# Glue.net
KiCad netlist of a schematic drawn in Altium Designer
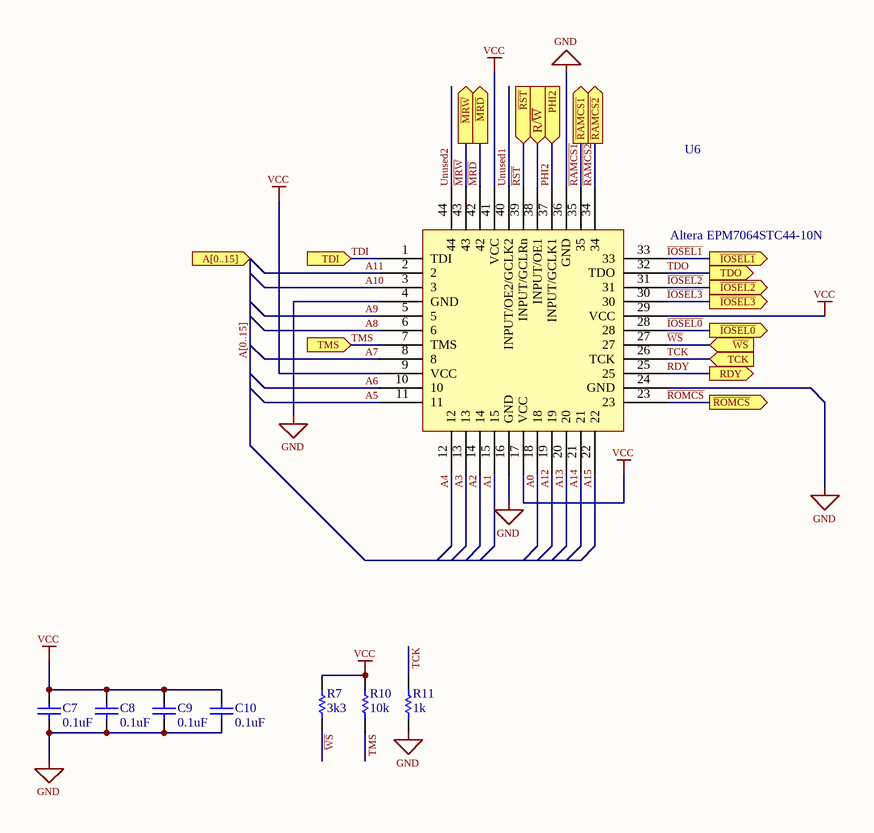
[diagram p0: Glue.SchDoc]

(export (version "E")
  (design (tool "Eeschema 10.0.6"))
  (components
    (comp (ref "C7")
      (value "0.1uF")
      (footprint "CAPC1608X90X35NL15T15")
      (description "0603 0.1uF Capacitor")
      (libsource (lib "Octopart library") (part "CAP-2"))
    )
    (comp (ref "C8")
      (value "0.1uF")
      (footprint "CAPC1608X90X35NL15T15")
      (description "0603 0.1uF Capacitor")
      (libsource (lib "Octopart library") (part "CAP-2"))
    )
    (comp (ref "C9")
      (value "0.1uF")
      (footprint "CAPC1608X90X35NL15T15")
      (description "0603 0.1uF Capacitor")
      (libsource (lib "Octopart library") (part "CAP-2"))
    )
    (comp (ref "C10")
      (value "0.1uF")
      (footprint "CAPC1608X90X35NL15T15")
      (description "0603 0.1uF Capacitor")
      (libsource (lib "Octopart library") (part "CAP-2"))
    )
    (comp (ref "R7")
      (value "3k3")
      (footprint "RESC1608X55X30ML20T10")
      (description "Thick Film Resistors - SMD 1/10watt 3.3Kohms 1%")
      (libsource (lib "CommunityVault") (part "RES-2"))
    )
    (comp (ref "R10")
      (value "10k")
      (footprint "RESC1609X50X30NL10T20")
      (description "Res Thick Film 0603 10K Ohm 1% 0.1W(1/10W) ±100ppm/C Molded SMD Automotive Paper T/R")
      (libsource (lib "CommunityVault") (part "CMP-2823404-2"))
    )
    (comp (ref "R11")
      (value "1k")
      (footprint "RESC1608X55X30NL15T15")
      (fields (field (name "MANUFACTURER PART NUMBER") "MCMR06X102 JTL"))
      (libsource (lib "CommunityVault") (part "CMP-a70b6f50b25278cc-3"))
    )
    (comp (ref "U6")
      (value "Altera EPM7064STC44-10N")
      (footprint "PCB-3kl8984h228uy08r94zq-1")
      (description "IC: CPLD; SMD; TQFP44; Series: Max 7000; Amount of macr")
      (libsource (lib "CommunityVault") (part "CMP-4ec387cff6eb9104-2"))
    )
  )
  (nets
    (net (code "1") (name "/A0") (class "Default")
      (node (ref "U6") (pin "18") (pinfunction "18_18") (pintype "passive"))
    )
    (net (code "2") (name "/A1") (class "Default")
      (node (ref "U6") (pin "15") (pinfunction "15_15") (pintype "passive"))
    )
    (net (code "3") (name "/A2") (class "Default")
      (node (ref "U6") (pin "14") (pinfunction "14_14") (pintype "passive"))
    )
    (net (code "4") (name "/A3") (class "Default")
      (node (ref "U6") (pin "13") (pinfunction "13_13") (pintype "passive"))
    )
    (net (code "5") (name "/A4") (class "Default")
      (node (ref "U6") (pin "12") (pinfunction "12_12") (pintype "passive"))
    )
    (net (code "6") (name "/A5") (class "Default")
      (node (ref "U6") (pin "11") (pinfunction "11_11") (pintype "passive"))
    )
    (net (code "7") (name "/A6") (class "Default")
      (node (ref "U6") (pin "10") (pinfunction "10_10") (pintype "passive"))
    )
    (net (code "8") (name "/A7") (class "Default")
      (node (ref "U6") (pin "8") (pinfunction "8_8") (pintype "passive"))
    )
    (net (code "9") (name "/A8") (class "Default")
      (node (ref "U6") (pin "6") (pinfunction "6_6") (pintype "passive"))
    )
    (net (code "10") (name "/A9") (class "Default")
      (node (ref "U6") (pin "5") (pinfunction "5_5") (pintype "passive"))
    )
    (net (code "11") (name "/A10") (class "Default")
      (node (ref "U6") (pin "3") (pinfunction "3_3") (pintype "passive"))
    )
    (net (code "12") (name "/A11") (class "Default")
      (node (ref "U6") (pin "2") (pinfunction "2_2") (pintype "passive"))
    )
    (net (code "13") (name "/A12") (class "Default")
      (node (ref "U6") (pin "19") (pinfunction "19_19") (pintype "passive"))
    )
    (net (code "14") (name "/A13") (class "Default")
      (node (ref "U6") (pin "20") (pinfunction "20_20") (pintype "passive"))
    )
    (net (code "15") (name "/A14") (class "Default")
      (node (ref "U6") (pin "21") (pinfunction "21_21") (pintype "passive"))
    )
    (net (code "16") (name "/A15") (class "Default")
      (node (ref "U6") (pin "22") (pinfunction "22_22") (pintype "passive"))
    )
    (net (code "18") (name "/PHI2") (class "Default")
      (node (ref "U6") (pin "37") (pinfunction "INPUT/GCLK1_37") (pintype "passive"))
    )
    (net (code "19") (name "/RDY") (class "Default")
      (node (ref "U6") (pin "25") (pinfunction "25_25") (pintype "passive"))
    )
    (net (code "20") (name "/R{slash}~{W}") (class "Default")
      (node (ref "U6") (pin "38") (pinfunction "INPUT/OE1_38") (pintype "passive"))
    )
    (net (code "21") (name "/TCK") (class "Default")
      (node (ref "R11") (pin "2") (pinfunction "2_2") (pintype "passive"))
      (node (ref "U6") (pin "26") (pinfunction "TCK_26") (pintype "passive"))
    )
    (net (code "22") (name "/TDI") (class "Default")
      (node (ref "U6") (pin "1") (pinfunction "TDI_1") (pintype "passive"))
    )
    (net (code "23") (name "/TDO") (class "Default")
      (node (ref "U6") (pin "32") (pinfunction "TDO_32") (pintype "passive"))
    )
    (net (code "24") (name "/TMS") (class "Default")
      (node (ref "R10") (pin "1") (pinfunction "1_1") (pintype "passive"))
      (node (ref "U6") (pin "7") (pinfunction "TMS_7") (pintype "passive"))
    )
    (net (code "25") (name "/Unused1") (class "Default")
      (node (ref "U6") (pin "40") (pinfunction "INPUT/OE2/GCLK2_40") (pintype "passive"))
    )
    (net (code "26") (name "/Unused2") (class "Default")
      (node (ref "U6") (pin "44") (pinfunction "44_44") (pintype "passive"))
    )
    (net (code "27") (name "/~{IOSEL0}") (class "Default")
      (node (ref "U6") (pin "28") (pinfunction "28_28") (pintype "passive"))
    )
    (net (code "28") (name "/~{IOSEL1}") (class "Default")
      (node (ref "U6") (pin "33") (pinfunction "33_33") (pintype "passive"))
    )
    (net (code "29") (name "/~{IOSEL2}") (class "Default")
      (node (ref "U6") (pin "31") (pinfunction "31_31") (pintype "passive"))
    )
    (net (code "30") (name "/~{IOSEL3}") (class "Default")
      (node (ref "U6") (pin "30") (pinfunction "30_30") (pintype "passive"))
    )
    (net (code "31") (name "/~{MRD}") (class "Default")
      (node (ref "U6") (pin "42") (pinfunction "42_42") (pintype "passive"))
    )
    (net (code "32") (name "/~{MRW}") (class "Default")
      (node (ref "U6") (pin "43") (pinfunction "43_43") (pintype "passive"))
    )
    (net (code "33") (name "/~{RAMCS1}") (class "Default")
      (node (ref "U6") (pin "35") (pinfunction "35_35") (pintype "passive"))
    )
    (net (code "34") (name "/~{RAMCS2}") (class "Default")
      (node (ref "U6") (pin "34") (pinfunction "34_34") (pintype "passive"))
    )
    (net (code "35") (name "/~{ROMCS}") (class "Default")
      (node (ref "U6") (pin "23") (pinfunction "23_23") (pintype "passive"))
    )
    (net (code "36") (name "/~{RST}") (class "Default")
      (node (ref "U6") (pin "39") (pinfunction "INPUT/GCLRn_39") (pintype "passive"))
    )
    (net (code "37") (name "/~{WS}") (class "Default")
      (node (ref "R7") (pin "2") (pinfunction "2_2") (pintype "passive"))
      (node (ref "U6") (pin "27") (pinfunction "27_27") (pintype "passive"))
    )
    (net (code "38") (name "GND") (class "Default")
      (node (ref "C10") (pin "2") (pinfunction "2_2") (pintype "passive"))
      (node (ref "C7") (pin "2") (pinfunction "2_2") (pintype "passive"))
      (node (ref "C8") (pin "2") (pinfunction "2_2") (pintype "passive"))
      (node (ref "C9") (pin "2") (pinfunction "2_2") (pintype "passive"))
      (node (ref "R11") (pin "1") (pinfunction "1_1") (pintype "passive"))
      (node (ref "U6") (pin "16") (pinfunction "GND_16") (pintype "passive"))
      (node (ref "U6") (pin "24") (pinfunction "GND_24") (pintype "passive"))
      (node (ref "U6") (pin "36") (pinfunction "GND_36") (pintype "passive"))
      (node (ref "U6") (pin "4") (pinfunction "GND_4") (pintype "passive"))
    )
    (net (code "39") (name "VCC") (class "Default")
      (node (ref "C10") (pin "1") (pinfunction "1_1") (pintype "passive"))
      (node (ref "C7") (pin "1") (pinfunction "1_1") (pintype "passive"))
      (node (ref "C8") (pin "1") (pinfunction "1_1") (pintype "passive"))
      (node (ref "C9") (pin "1") (pinfunction "1_1") (pintype "passive"))
      (node (ref "R10") (pin "2") (pinfunction "2_2") (pintype "passive"))
      (node (ref "R7") (pin "1") (pinfunction "1_1") (pintype "passive"))
      (node (ref "U6") (pin "17") (pinfunction "VCC_17") (pintype "passive"))
      (node (ref "U6") (pin "29") (pinfunction "VCC_29") (pintype "passive"))
      (node (ref "U6") (pin "41") (pinfunction "VCC_41") (pintype "passive"))
      (node (ref "U6") (pin "9") (pinfunction "VCC_9") (pintype "passive"))
    )
  )
)
